# raiden_application.net
KiCad netlist of a schematic drawn in EasyEDA
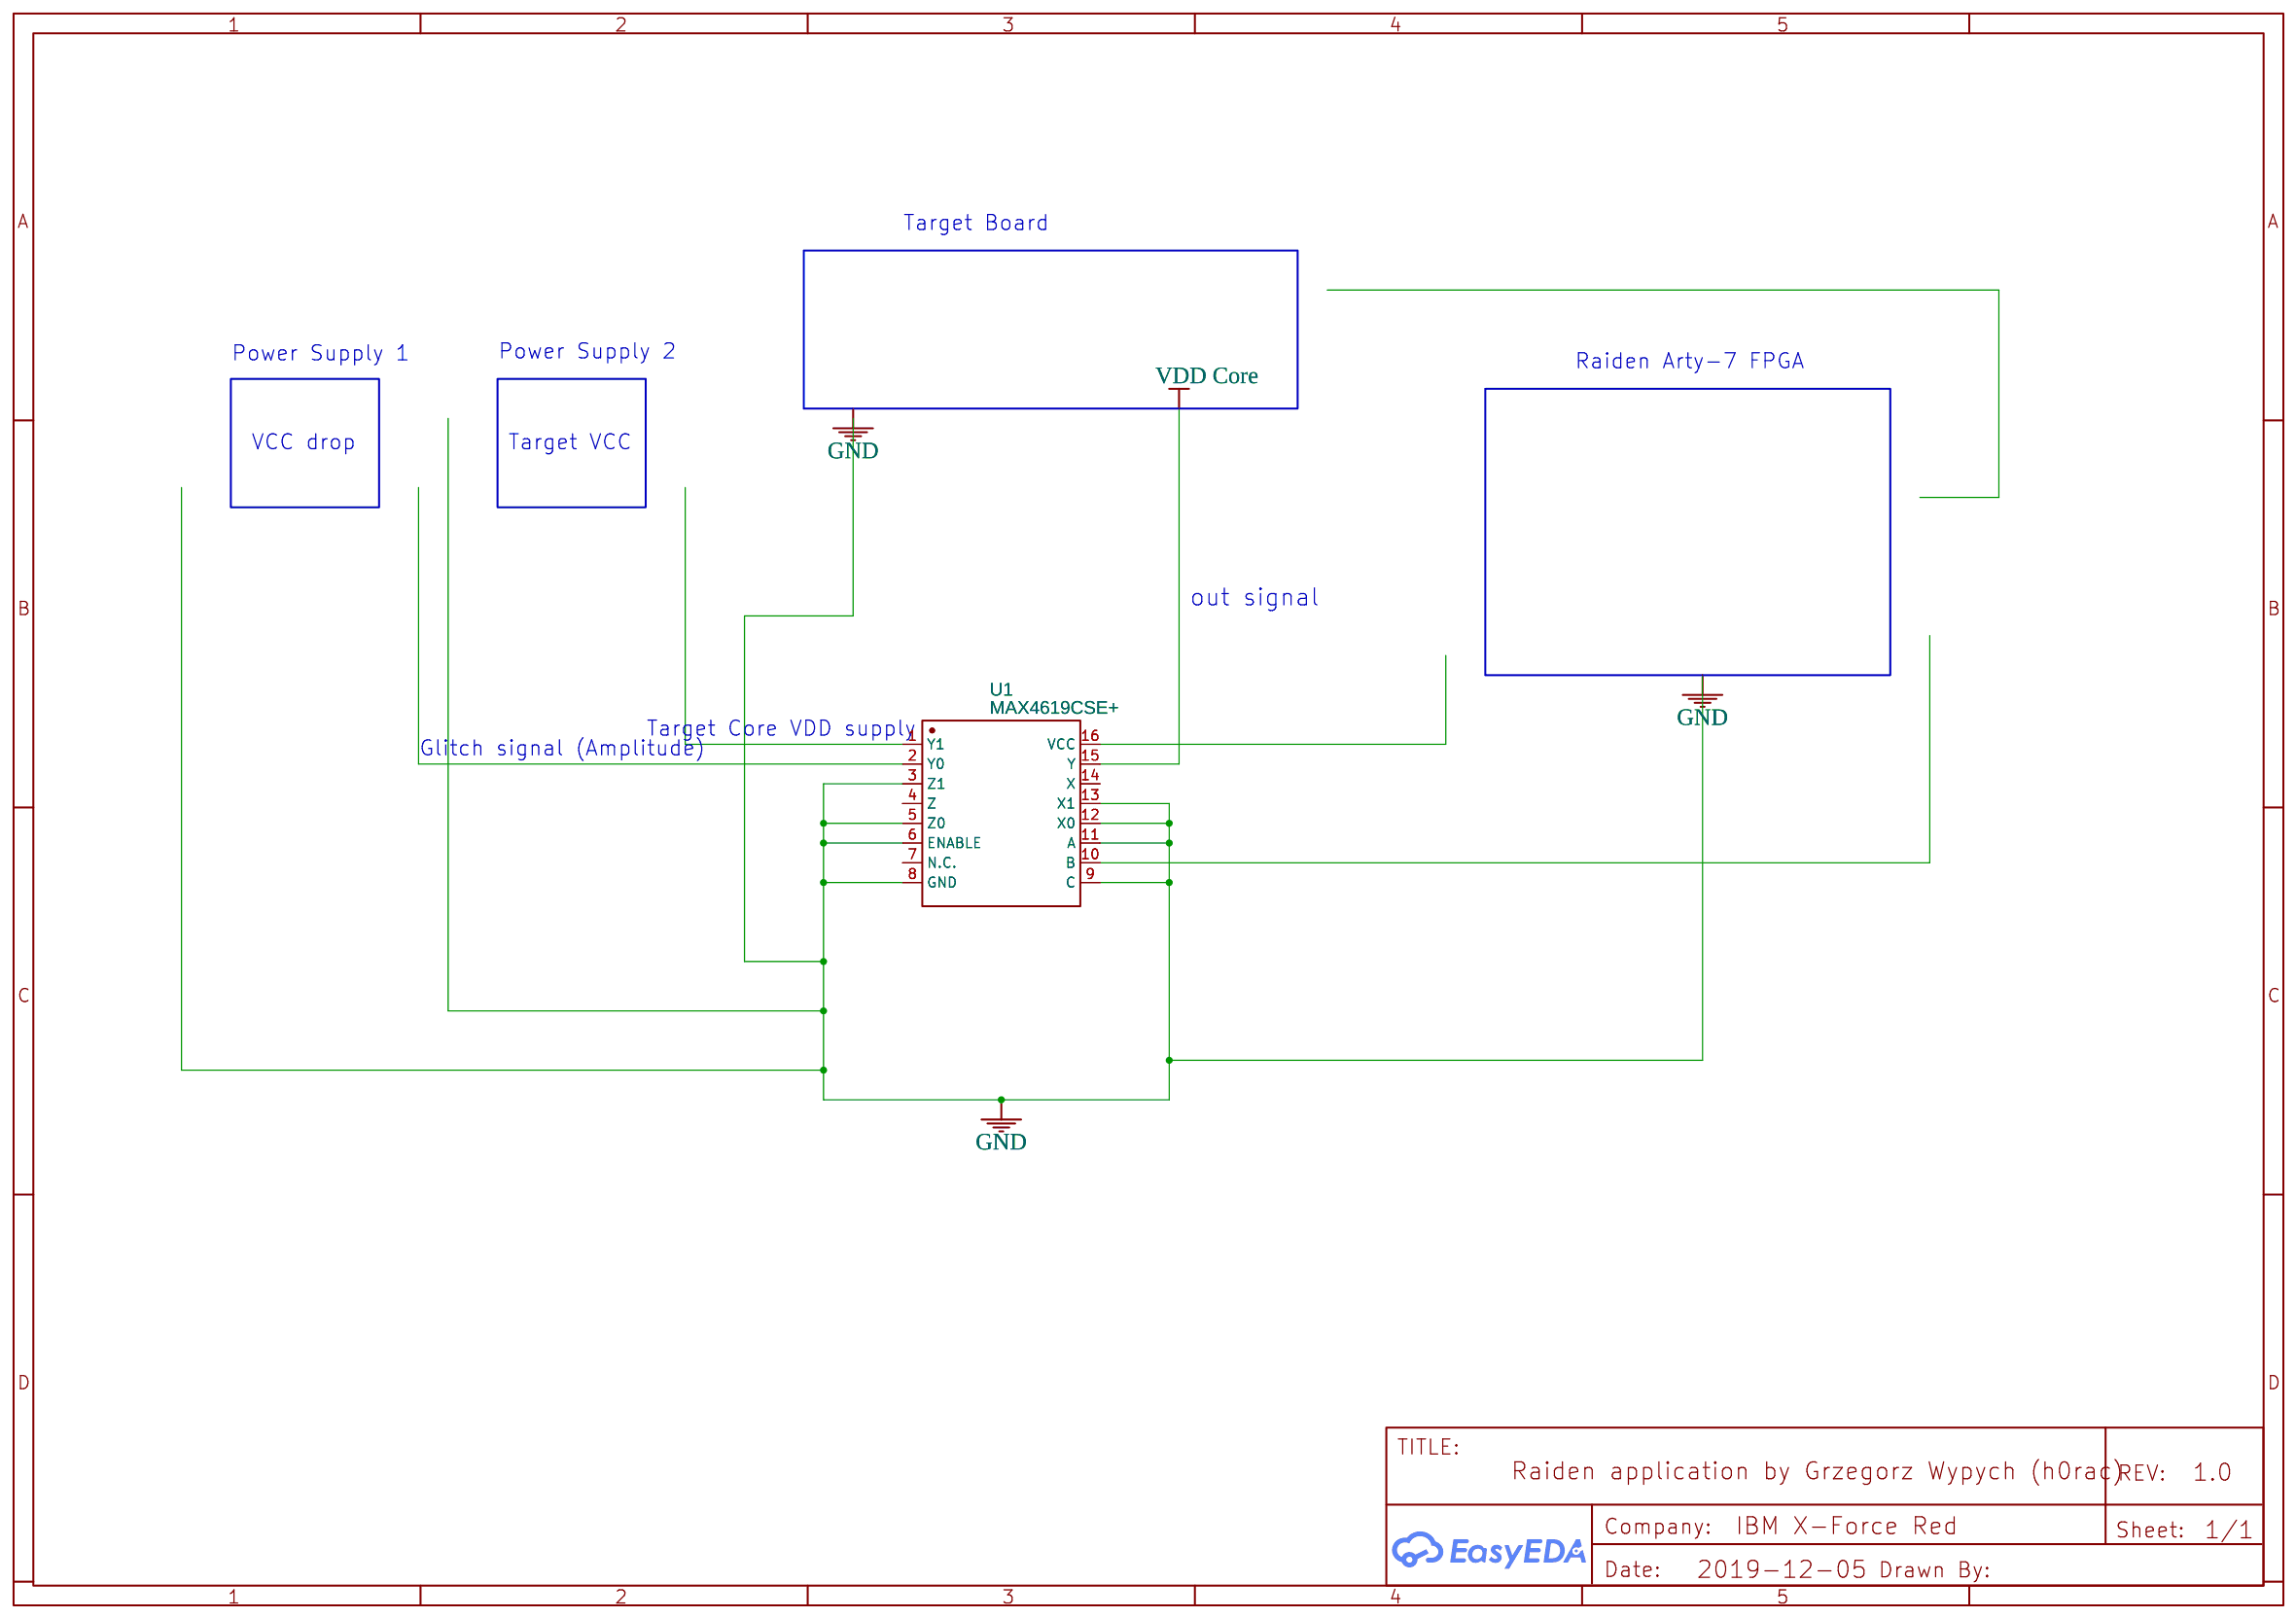
[diagram p0: schematic sheet]

(export (version "E")
  (design (tool "Eeschema 10.0.6"))
  (components
    (comp (ref "U1")
      (value "MAX4619CSE+")
      (fields
        (field (name "BOM_Manufacturer Part") "MAX4617CSE+")
        (field (name "BOM_Supplier Part") "C143482")
      )
      (libsource (lib "") (part "Unknown_500_405"))
    )
  )
  (nets
    (net (code "1") (name "GND") (class "Default")
      (node (ref "U1") (pin "11") (pinfunction "A_11") (pintype "unspecified"))
      (node (ref "U1") (pin "12") (pinfunction "X0_12") (pintype "unspecified"))
      (node (ref "U1") (pin "13") (pinfunction "X1_13") (pintype "unspecified"))
      (node (ref "U1") (pin "3") (pinfunction "Z1_3") (pintype "unspecified"))
      (node (ref "U1") (pin "5") (pinfunction "Z0_5") (pintype "unspecified"))
      (node (ref "U1") (pin "6") (pinfunction "ENABLE_6") (pintype "unspecified"))
      (node (ref "U1") (pin "8") (pinfunction "GND_8") (pintype "unspecified"))
      (node (ref "U1") (pin "9") (pinfunction "C_9") (pintype "unspecified"))
    )
    (net (code "2") (name "VDD Core") (class "Default")
      (node (ref "U1") (pin "15") (pinfunction "Y_15") (pintype "unspecified"))
    )
    (net (code "3") (name "unconnected-(U1-B-Pad10)") (class "Default")
      (node (ref "U1") (pin "10") (pinfunction "B_10") (pintype "unspecified"))
    )
    (net (code "4") (name "unconnected-(U1-N.C.-Pad7)") (class "Default")
      (node (ref "U1") (pin "7") (pinfunction "N.C._7") (pintype "unspecified"))
    )
    (net (code "5") (name "unconnected-(U1-VCC-Pad16)") (class "Default")
      (node (ref "U1") (pin "16") (pinfunction "VCC_16") (pintype "unspecified"))
    )
    (net (code "6") (name "unconnected-(U1-X-Pad14)") (class "Default")
      (node (ref "U1") (pin "14") (pinfunction "X_14") (pintype "unspecified"))
    )
    (net (code "7") (name "unconnected-(U1-Y0-Pad2)") (class "Default")
      (node (ref "U1") (pin "2") (pinfunction "Y0_2") (pintype "unspecified"))
    )
    (net (code "8") (name "unconnected-(U1-Y1-Pad1)") (class "Default")
      (node (ref "U1") (pin "1") (pinfunction "Y1_1") (pintype "unspecified"))
    )
    (net (code "9") (name "unconnected-(U1-Z-Pad4)") (class "Default")
      (node (ref "U1") (pin "4") (pinfunction "Z_4") (pintype "unspecified"))
    )
  )
)
